# Microcontroller.net
KiCad netlist of a schematic drawn in Altium Designer
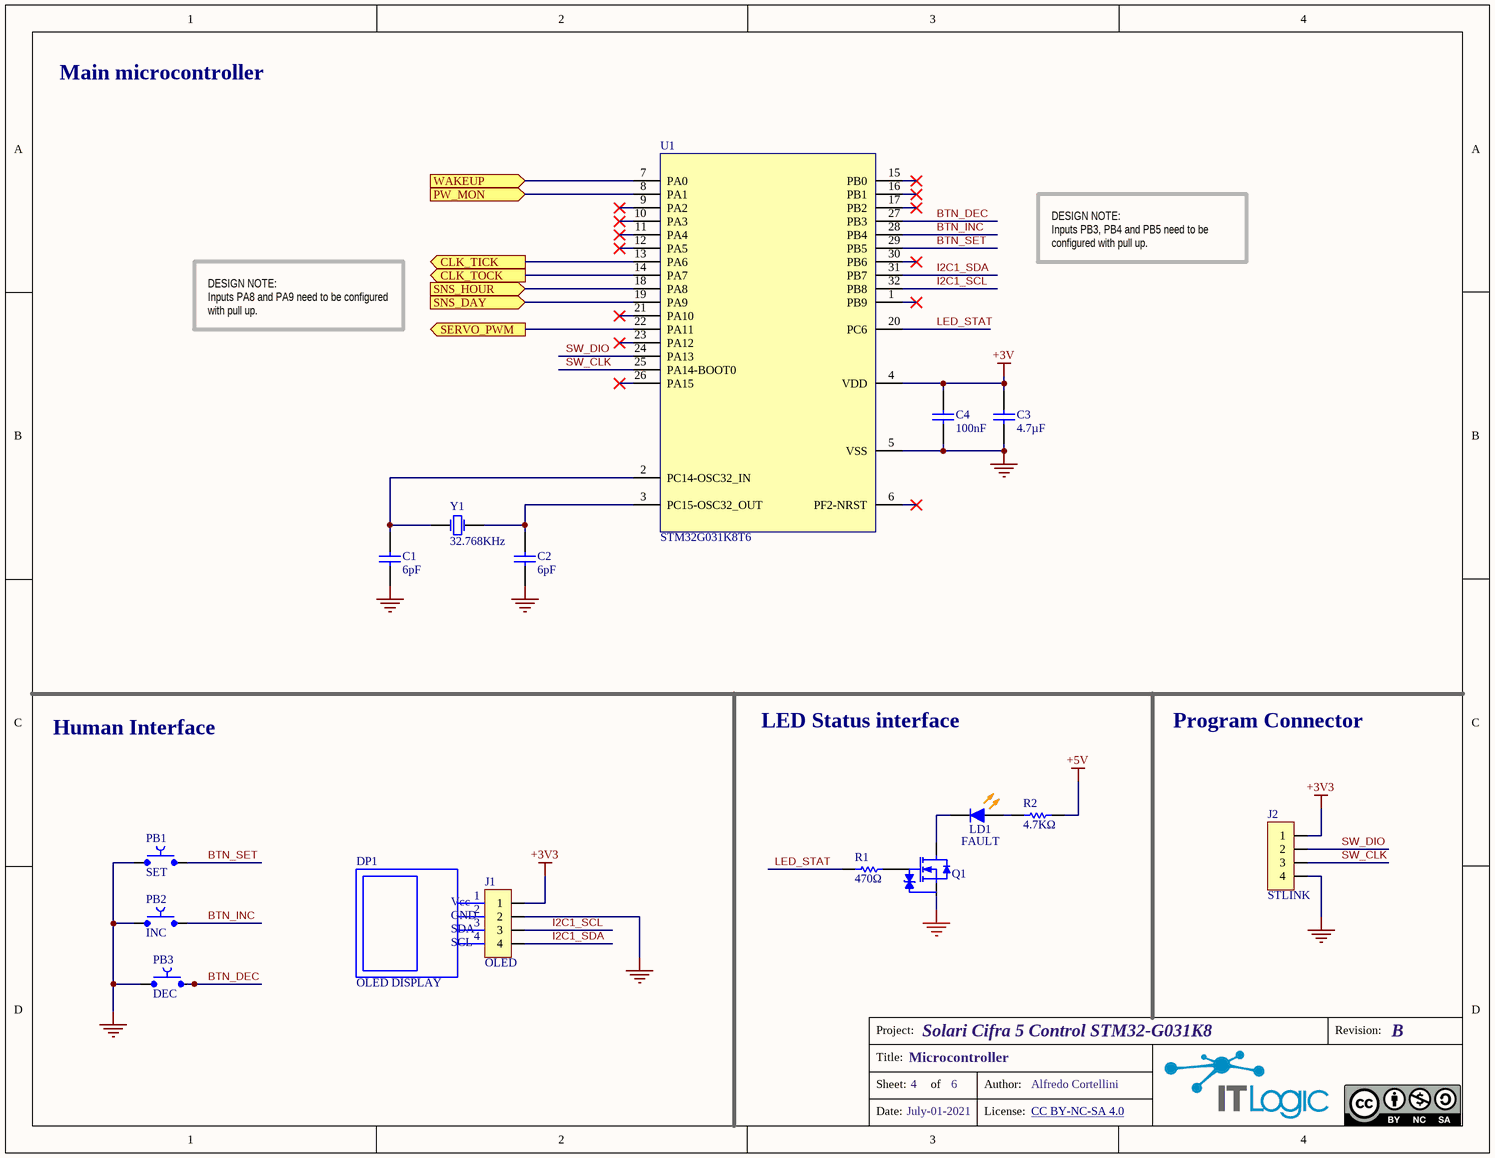
[diagram p0: Microcontroller.SchDoc]

(export (version "E")
  (design (tool "Eeschema 10.0.6"))
  (components
    (comp (ref "C1")
      (value "6pF")
      (footprint "C0603-H90")
      (description "Cap 0603 Case Ceramic 6pF 50V C0G")
      (fields
        (field (name "MANUFACTURER") "TDK")
        (field (name "MANUFACTURER PART NUMBER") "CGA3E2C0G1H060D080AA")
      )
      (libsource (lib "IT Logic Library") (part "CGA3E2C0G1H060D080AA"))
    )
    (comp (ref "C2")
      (value "6pF")
      (footprint "C0603-H90")
      (description "Cap 0603 Case Ceramic 6pF 50V C0G")
      (fields
        (field (name "MANUFACTURER") "TDK")
        (field (name "MANUFACTURER PART NUMBER") "CGA3E2C0G1H060D080AA")
      )
      (libsource (lib "IT Logic Library") (part "CGA3E2C0G1H060D080AA"))
    )
    (comp (ref "C3")
      (value "4.7µF")
      (footprint "C0603-H90")
      (description "Cap 0603 Case Ceramic 4.7uF 10V X7S")
      (fields
        (field (name "MANUFACTURER") "TDK")
        (field (name "MANUFACTURER PART NUMBER") "C1608X7S1A475K080AC")
      )
      (libsource (lib "IT Logic Library") (part "C1608X7S1A475K080AC"))
    )
    (comp (ref "C4")
      (value "100nF")
      (footprint "C0603-H90")
      (description "Cap 0603 Case Ceramic 100nF 50V X7R")
      (fields
        (field (name "MANUFACTURER") "TDK")
        (field (name "MANUFACTURER PART NUMBER") "CGA3E2X7R1H104K080AA")
      )
      (libsource (lib "IT Logic Library") (part "CGA3E2X7R1H104K080AA"))
    )
    (comp (ref "DP1")
      (value "OLED DISPLAY")
      (description "Oled Module, 0.96inch, I2C Interface")
      (fields (field (name "MANUFACTURER") "Hiletgo") (field (name "MANUFACTURER PART NUMBER") "MC096VW"))
      (libsource (lib "IT Logic Library") (part "MC096VW"))
    )
    (comp (ref "J1")
      (value "OLED")
      (footprint "SSQ-104-01-S-BOTTOM")
      (description "Conn Post Socket Header Vert - 1 Row - 4 Pos - 3 mm Lenght - Tin")
      (fields
        (field (name "MANUFACTURER") "Samtec")
        (field (name "MANUFACTURER PART NUMBER") "SSQ-104-01-T-S")
      )
      (libsource (lib "IT Logic Library") (part "SSQ-104-01-T-S"))
    )
    (comp (ref "J2")
      (value "STLINK")
      (footprint "HDR-V-1R-04P-5.8L")
      (description "Breakaway Header Vert - 1 Row - 4 Pos - 6 mm Lenght - Gold")
      (fields (field (name "MANUFACTURER") "Molex") (field (name "MANUFACTURER PART NUMBER") "22-28-4043"))
      (libsource (lib "IT Logic Library") (part "22-28-4043"))
    )
    (comp (ref "LD1")
      (value "FAULT")
      (footprint "LED-0805-O")
      (description "LED 0805 Top Orange 605nm 2-Pin")
      (fields
        (field (name "MANUFACTURER") "Vishay Lite-On")
        (field (name "MANUFACTURER PART NUMBER") "LTST-C170KFKT")
      )
      (libsource (lib "IT Logic Library") (part "LTST-C170KFKT"))
    )
    (comp (ref "PB1")
      (value "SET")
      (footprint "BUT-1-1825027-1-BOTTOM")
      (description "Tactile Switch, Round Stem, Color ivory, Lenght 5.74mm, Right Angle, Through Hole.")
      (fields
        (field (name "MANUFACTURER") "TE Connectivity")
        (field (name "MANUFACTURER PART NUMBER") "1-1825027-1")
      )
      (libsource (lib "IT Logic Library") (part "1-1825027-1"))
    )
    (comp (ref "PB2")
      (value "INC")
      (footprint "BUT-1-1825027-1-BOTTOM")
      (description "Tactile Switch, Round Stem, Color ivory, Lenght 5.74mm, Right Angle, Through Hole.")
      (fields
        (field (name "MANUFACTURER") "TE Connectivity")
        (field (name "MANUFACTURER PART NUMBER") "1-1825027-1")
      )
      (libsource (lib "IT Logic Library") (part "1-1825027-1"))
    )
    (comp (ref "PB3")
      (value "DEC")
      (footprint "BUT-1-1825027-1-BOTTOM")
      (description "Tactile Switch, Round Stem, Color ivory, Lenght 5.74mm, Right Angle, Through Hole.")
      (fields
        (field (name "MANUFACTURER") "TE Connectivity")
        (field (name "MANUFACTURER PART NUMBER") "1-1825027-1")
      )
      (libsource (lib "IT Logic Library") (part "1-1825027-1"))
    )
    (comp (ref "Q1")
      (value "BSS138K-13")
      (footprint "SOT-23")
      (description "Mosfet N 50V Vds 20V Vgs ESD 1.4R SOT-23")
      (fields (field (name "MANUFACTURER") "Diodes"))
      (libsource (lib "IT Logic Library") (part "BSS138K-13"))
    )
    (comp (ref "R1")
      (value "470Ω")
      (footprint "R0603-H55")
      (description "Resistor 0603 Case 470R 1% 1/10W")
      (fields
        (field (name "MANUFACTURER") "Yageo")
        (field (name "MANUFACTURER PART NUMBER") "RC0603FR-07470RL")
      )
      (libsource (lib "IT Logic Library") (part "RC0603FR-07470RL"))
    )
    (comp (ref "R2")
      (value "4.7KΩ")
      (footprint "R0603-H55")
      (description "Resistor 0603 Case 4.7KR 1% 1/10W")
      (fields
        (field (name "MANUFACTURER") "Yageo")
        (field (name "MANUFACTURER PART NUMBER") "RC0603FR-074K7L")
      )
      (libsource (lib "IT Logic Library") (part "RC0603FR-074K7L"))
    )
    (comp (ref "U1")
      (value "STM32G031K8T6")
      (footprint "LQFP32-7X7-P080")
      (description "STM32 Arm Cortex-M0+ MCU, 64 Kbytes Flash 8 Kbytes RAM, 64 MHz CPU, Package LQFP32")
      (fields (field (name "MANUFACTURER") "STMicroelectronics"))
      (libsource (lib "IT Logic Library") (part "STM32G031K8T6"))
    )
    (comp (ref "Y1")
      (value "32.768KHz")
      (footprint "XTAL-ABM6")
      (description "Quartz 32.768kHz ±10ppm Crystal 6pF 90 kOhm -40°C ~ 85°C  Surface Mount 2-SMD")
      (fields
        (field (name "MANUFACTURER") "Abracon")
        (field (name "MANUFACTURER PART NUMBER") "ABS06-32.768KHZ-6-1-T")
      )
      (libsource (lib "IT Logic Library") (part "ABS06-32.768KHZ-6-1-T"))
    )
  )
  (nets
    (net (code "1") (name "+3V") (class "Default")
      (node (ref "C3") (pin "2") (pinfunction "2_2") (pintype "passive"))
      (node (ref "C4") (pin "2") (pinfunction "2_2") (pintype "passive"))
      (node (ref "U1") (pin "4") (pinfunction "VDD_4") (pintype "power_in"))
    )
    (net (code "2") (name "+3V3") (class "Default")
      (node (ref "J1") (pin "1") (pinfunction "1_1") (pintype "passive"))
      (node (ref "J2") (pin "1") (pinfunction "1_1") (pintype "passive"))
    )
    (net (code "3") (name "+5V") (class "Default")
      (node (ref "R2") (pin "2") (pinfunction "2_2") (pintype "passive"))
    )
    (net (code "4") (name "/BTN_DEC") (class "Default")
      (node (ref "PB3") (pin "2") (pinfunction "2_2") (pintype "passive"))
      (node (ref "U1") (pin "27") (pinfunction "PB3_27") (pintype "passive"))
    )
    (net (code "5") (name "/BTN_INC") (class "Default")
      (node (ref "PB2") (pin "2") (pinfunction "2_2") (pintype "passive"))
      (node (ref "U1") (pin "28") (pinfunction "PB4_28") (pintype "passive"))
    )
    (net (code "6") (name "/BTN_SET") (class "Default")
      (node (ref "PB1") (pin "2") (pinfunction "2_2") (pintype "passive"))
      (node (ref "U1") (pin "29") (pinfunction "PB5_29") (pintype "passive"))
    )
    (net (code "7") (name "/CLK_TICK") (class "Default")
      (node (ref "U1") (pin "13") (pinfunction "PA6_13") (pintype "passive"))
    )
    (net (code "8") (name "/CLK_TOCK") (class "Default")
      (node (ref "U1") (pin "14") (pinfunction "PA7_14") (pintype "passive"))
    )
    (net (code "9") (name "/I2C1_SCL") (class "Default")
      (node (ref "J1") (pin "3") (pinfunction "3_3") (pintype "passive"))
      (node (ref "U1") (pin "32") (pinfunction "PB8_32") (pintype "passive"))
    )
    (net (code "10") (name "/I2C1_SDA") (class "Default")
      (node (ref "J1") (pin "4") (pinfunction "4_4") (pintype "passive"))
      (node (ref "U1") (pin "31") (pinfunction "PB7_31") (pintype "passive"))
    )
    (net (code "11") (name "/LED_STAT") (class "Default")
      (node (ref "R1") (pin "1") (pinfunction "1_1") (pintype "passive"))
      (node (ref "U1") (pin "20") (pinfunction "PC6_20") (pintype "passive"))
    )
    (net (code "12") (name "/PW_MON") (class "Default")
      (node (ref "U1") (pin "8") (pinfunction "PA1_8") (pintype "passive"))
    )
    (net (code "13") (name "/SERVO_PWM") (class "Default")
      (node (ref "U1") (pin "22") (pinfunction "PA11_22") (pintype "passive"))
    )
    (net (code "14") (name "/SNS_DAY") (class "Default")
      (node (ref "U1") (pin "19") (pinfunction "PA9_19") (pintype "passive"))
    )
    (net (code "15") (name "/SNS_HOUR") (class "Default")
      (node (ref "U1") (pin "18") (pinfunction "PA8_18") (pintype "passive"))
    )
    (net (code "16") (name "/SW_CLK") (class "Default")
      (node (ref "J2") (pin "3") (pinfunction "3_3") (pintype "passive"))
      (node (ref "U1") (pin "25") (pinfunction "PA14-BOOT0_25") (pintype "passive"))
    )
    (net (code "17") (name "/SW_DIO") (class "Default")
      (node (ref "J2") (pin "2") (pinfunction "2_2") (pintype "passive"))
      (node (ref "U1") (pin "24") (pinfunction "PA13_24") (pintype "passive"))
    )
    (net (code "18") (name "/WAKEUP") (class "Default")
      (node (ref "U1") (pin "7") (pinfunction "PA0_7") (pintype "passive"))
    )
    (net (code "19") (name "GND") (class "Default")
      (node (ref "C1") (pin "1") (pinfunction "1_1") (pintype "passive"))
      (node (ref "C2") (pin "1") (pinfunction "1_1") (pintype "passive"))
      (node (ref "C3") (pin "1") (pinfunction "1_1") (pintype "passive"))
      (node (ref "C4") (pin "1") (pinfunction "1_1") (pintype "passive"))
      (node (ref "J1") (pin "2") (pinfunction "2_2") (pintype "passive"))
      (node (ref "J2") (pin "4") (pinfunction "4_4") (pintype "passive"))
      (node (ref "PB1") (pin "1") (pinfunction "1_1") (pintype "passive"))
      (node (ref "PB2") (pin "1") (pinfunction "1_1") (pintype "passive"))
      (node (ref "PB3") (pin "1") (pinfunction "1_1") (pintype "passive"))
      (node (ref "Q1") (pin "2") (pinfunction "S_2") (pintype "passive"))
      (node (ref "U1") (pin "5") (pinfunction "VSS_5") (pintype "power_in"))
    )
    (net (code "20") (name "Net-(LD1-A)") (class "Default")
      (node (ref "LD1") (pin "2") (pinfunction "A_2") (pintype "passive"))
      (node (ref "R2") (pin "1") (pinfunction "1_1") (pintype "passive"))
    )
    (net (code "21") (name "Net-(LD1-K)") (class "Default")
      (node (ref "LD1") (pin "1") (pinfunction "K_1") (pintype "passive"))
      (node (ref "Q1") (pin "3") (pinfunction "D_3") (pintype "passive"))
    )
    (net (code "22") (name "Net-(Q1-G)") (class "Default")
      (node (ref "Q1") (pin "1") (pinfunction "G_1") (pintype "passive"))
      (node (ref "R1") (pin "2") (pinfunction "2_2") (pintype "passive"))
    )
    (net (code "23") (name "Net-(U1-PC14-OSC32_IN)") (class "Default")
      (node (ref "C1") (pin "2") (pinfunction "2_2") (pintype "passive"))
      (node (ref "U1") (pin "2") (pinfunction "PC14-OSC32_IN_2") (pintype "passive"))
      (node (ref "Y1") (pin "1") (pinfunction "X1_1") (pintype "passive"))
    )
    (net (code "24") (name "Net-(U1-PC15-OSC32_OUT)") (class "Default")
      (node (ref "C2") (pin "2") (pinfunction "2_2") (pintype "passive"))
      (node (ref "U1") (pin "3") (pinfunction "PC15-OSC32_OUT_3") (pintype "passive"))
      (node (ref "Y1") (pin "2") (pinfunction "X2_2") (pintype "passive"))
    )
    (net (code "25") (name "unconnected-(U1-PA2-Pad9)") (class "Default")
      (node (ref "U1") (pin "9") (pinfunction "PA2_9") (pintype "passive+no_connect"))
    )
    (net (code "26") (name "unconnected-(U1-PA3-Pad10)") (class "Default")
      (node (ref "U1") (pin "10") (pinfunction "PA3_10") (pintype "passive+no_connect"))
    )
    (net (code "27") (name "unconnected-(U1-PA4-Pad11)") (class "Default")
      (node (ref "U1") (pin "11") (pinfunction "PA4_11") (pintype "passive+no_connect"))
    )
    (net (code "28") (name "unconnected-(U1-PA5-Pad12)") (class "Default")
      (node (ref "U1") (pin "12") (pinfunction "PA5_12") (pintype "passive+no_connect"))
    )
    (net (code "29") (name "unconnected-(U1-PA10-Pad21)") (class "Default")
      (node (ref "U1") (pin "21") (pinfunction "PA10_21") (pintype "passive+no_connect"))
    )
    (net (code "30") (name "unconnected-(U1-PA12-Pad23)") (class "Default")
      (node (ref "U1") (pin "23") (pinfunction "PA12_23") (pintype "passive+no_connect"))
    )
    (net (code "31") (name "unconnected-(U1-PA15-Pad26)") (class "Default")
      (node (ref "U1") (pin "26") (pinfunction "PA15_26") (pintype "passive+no_connect"))
    )
    (net (code "32") (name "unconnected-(U1-PB0-Pad15)") (class "Default")
      (node (ref "U1") (pin "15") (pinfunction "PB0_15") (pintype "passive+no_connect"))
    )
    (net (code "33") (name "unconnected-(U1-PB1-Pad16)") (class "Default")
      (node (ref "U1") (pin "16") (pinfunction "PB1_16") (pintype "passive+no_connect"))
    )
    (net (code "34") (name "unconnected-(U1-PB2-Pad17)") (class "Default")
      (node (ref "U1") (pin "17") (pinfunction "PB2_17") (pintype "passive+no_connect"))
    )
    (net (code "35") (name "unconnected-(U1-PB6-Pad30)") (class "Default")
      (node (ref "U1") (pin "30") (pinfunction "PB6_30") (pintype "passive+no_connect"))
    )
    (net (code "36") (name "unconnected-(U1-PB9-Pad1)") (class "Default")
      (node (ref "U1") (pin "1") (pinfunction "PB9_1") (pintype "passive+no_connect"))
    )
    (net (code "37") (name "unconnected-(U1-PF2-NRST-Pad6)") (class "Default")
      (node (ref "U1") (pin "6") (pinfunction "PF2-NRST_6") (pintype "passive+no_connect"))
    )
  )
)
